# I2C-LX.net
KiCad netlist of a schematic drawn in Altium Designer
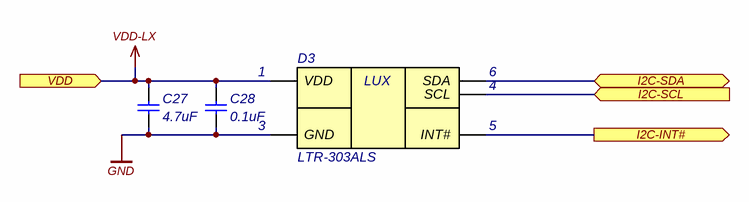
[diagram p0: I2C-LX.SchDoc]

(export (version "E")
  (design (tool "Eeschema 10.0.6"))
  (components
    (comp (ref "C27")
      (value "4.7uF")
      (footprint "C0402")
      (fields
        (field (name "PART NUMBER") "0402-X5R-6.3V-4.7uF±20%")
        (field (name "VOLTAGE") "6.3V")
        (field (name "TOLERANCE") "20%")
      )
      (libsource (lib "ATB") (part "C"))
    )
    (comp (ref "C28")
      (value "0.1uF")
      (footprint "C0402")
      (fields
        (field (name "PART NUMBER") "0402-X7R-16V-0.1uF±10%")
        (field (name "VOLTAGE") "16V")
        (field (name "TOLERANCE") "5%")
      )
      (libsource (lib "ATB") (part "C"))
    )
    (comp (ref "D3")
      (value "LTR-303ALS")
      (footprint "ChipLED-6")
      (description "I2C Ambient Light Sensor ChipLED-6")
      (fields (field (name "MANUFACTURER") "Lite-On"))
      (libsource (lib "ATB") (part "LTR-303ALS"))
    )
  )
  (nets
    (net (code "1") (name "/I2C-INT#") (class "Default")
      (node (ref "D3") (pin "5") (pinfunction "INT#_5") (pintype "passive"))
    )
    (net (code "2") (name "/I2C-SCL") (class "Default")
      (node (ref "D3") (pin "4") (pinfunction "SCL_4") (pintype "passive"))
    )
    (net (code "3") (name "/I2C-SDA") (class "Default")
      (node (ref "D3") (pin "6") (pinfunction "SDA_6") (pintype "passive"))
    )
    (net (code "4") (name "GND") (class "Default")
      (node (ref "C27") (pin "1") (pinfunction "1_1") (pintype "passive"))
      (node (ref "C28") (pin "1") (pinfunction "1_1") (pintype "passive"))
      (node (ref "D3") (pin "3") (pinfunction "GND_3") (pintype "passive"))
    )
    (net (code "5") (name "VDD-LX") (class "Default")
      (node (ref "C27") (pin "2") (pinfunction "2_2") (pintype "passive"))
      (node (ref "C28") (pin "2") (pinfunction "2_2") (pintype "passive"))
      (node (ref "D3") (pin "1") (pinfunction "VDD_1") (pintype "passive"))
    )
  )
)
